# cheerlights.net
KiCad netlist of a schematic drawn in EAGLE
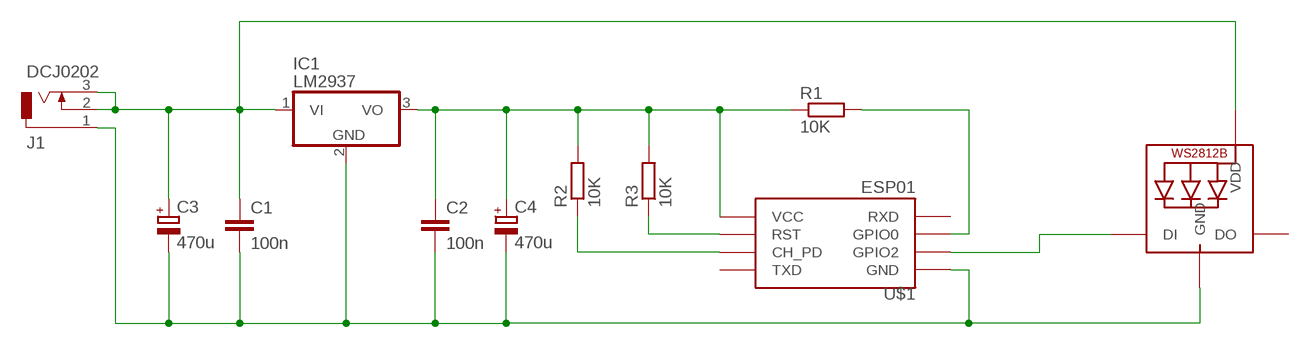
[diagram p0: schematic, sheet 1]

(export (version "E")
  (design (tool "Eeschema 10.0.6"))
  (components
    (comp (ref "C1")
      (value "100n")
      (footprint "eagle-import:C050-025X075")
      (libsource (lib "eagle-import") (part "C-EU050-025X075"))
    )
    (comp (ref "C2")
      (value "100n")
      (footprint "eagle-import:C050-025X075")
      (libsource (lib "eagle-import") (part "C-EU050-025X075"))
    )
    (comp (ref "C3")
      (value "470u")
      (footprint "eagle-import:E5-10,5")
      (libsource (lib "eagle-import") (part "CPOL-EUE5-10.5"))
    )
    (comp (ref "C4")
      (value "470u")
      (footprint "eagle-import:E5-10,5")
      (libsource (lib "eagle-import") (part "CPOL-EUE5-10.5"))
    )
    (comp (ref "IC1")
      (value "LM2937")
      (footprint "eagle-import:TO220H")
      (libsource (lib "eagle-import") (part "78T05"))
    )
    (comp (ref "J1")
      (value "DCJ0202")
      (footprint "eagle-import:DCJ0202")
      (libsource (lib "eagle-import") (part "DCJ0202"))
    )
    (comp (ref "LED1")
      (value "WS2812B_5050N")
      (footprint "eagle-import:WS2812B-NARROW")
      (libsource (lib "eagle-import") (part "WS2812B_5050N"))
    )
    (comp (ref "R1")
      (value "10K")
      (footprint "eagle-import:0207_10")
      (libsource (lib "eagle-import") (part "R-EU_0207/10"))
    )
    (comp (ref "R2")
      (value "10K")
      (footprint "eagle-import:0207_15")
      (libsource (lib "eagle-import") (part "R-EU_0207/15"))
    )
    (comp (ref "R3")
      (value "10K")
      (footprint "eagle-import:0207_15")
      (libsource (lib "eagle-import") (part "R-EU_0207/15"))
    )
    (comp (ref "U$1")
      (value "ESP01")
      (footprint "eagle-import:ESP01")
      (libsource (lib "eagle-import") (part "ESP01"))
    )
  )
  (nets
    (net (code "1") (name "Net-(IC1-GND)") (class "Default")
      (node (ref "C1") (pin "2") (pinfunction "2_2") (pintype "passive"))
      (node (ref "C2") (pin "2") (pinfunction "2_2") (pintype "passive"))
      (node (ref "C3") (pin "-") (pinfunction "-_-") (pintype "passive"))
      (node (ref "C4") (pin "-") (pinfunction "-_-") (pintype "passive"))
      (node (ref "IC1") (pin "2") (pinfunction "GND_2") (pintype "passive"))
      (node (ref "J1") (pin "1") (pinfunction "1_1") (pintype "passive"))
      (node (ref "LED1") (pin "3-GND") (pinfunction "GND_3-GND") (pintype "power_in"))
      (node (ref "U$1") (pin "GND") (pinfunction "GND_GND") (pintype "bidirectional"))
    )
    (net (code "2") (name "Net-(IC1-VI)") (class "Default")
      (node (ref "C1") (pin "1") (pinfunction "1_1") (pintype "passive"))
      (node (ref "C3") (pin "+") (pinfunction "+_+") (pintype "passive"))
      (node (ref "IC1") (pin "1") (pinfunction "VI_1") (pintype "input"))
      (node (ref "J1") (pin "2") (pinfunction "2_2") (pintype "passive"))
      (node (ref "J1") (pin "3") (pinfunction "3_3") (pintype "passive"))
      (node (ref "LED1") (pin "1-VDD") (pinfunction "VDD_1-VDD") (pintype "power_in"))
    )
    (net (code "3") (name "Net-(IC1-VO)") (class "Default")
      (node (ref "C2") (pin "1") (pinfunction "1_1") (pintype "passive"))
      (node (ref "C4") (pin "+") (pinfunction "+_+") (pintype "passive"))
      (node (ref "IC1") (pin "3") (pinfunction "VO_3") (pintype "passive"))
      (node (ref "R1") (pin "1") (pinfunction "1_1") (pintype "passive"))
      (node (ref "R2") (pin "2") (pinfunction "2_2") (pintype "passive"))
      (node (ref "R3") (pin "2") (pinfunction "2_2") (pintype "passive"))
      (node (ref "U$1") (pin "VCC") (pinfunction "VCC_VCC") (pintype "bidirectional"))
    )
    (net (code "4") (name "Net-(LED1-DI)") (class "Default")
      (node (ref "LED1") (pin "4-DIN") (pinfunction "DI_4-DIN") (pintype "input"))
      (node (ref "U$1") (pin "GPIO2") (pinfunction "GPIO2_GPIO2") (pintype "bidirectional"))
    )
    (net (code "5") (name "Net-(R1-Pad2)") (class "Default")
      (node (ref "R1") (pin "2") (pinfunction "2_2") (pintype "passive"))
      (node (ref "U$1") (pin "GPIO0") (pinfunction "GPIO0_GPIO0") (pintype "bidirectional"))
    )
    (net (code "6") (name "Net-(R2-Pad1)") (class "Default")
      (node (ref "R2") (pin "1") (pinfunction "1_1") (pintype "passive"))
      (node (ref "U$1") (pin "CH_PD") (pinfunction "CH_PD_CH_PD") (pintype "bidirectional"))
    )
    (net (code "7") (name "Net-(R3-Pad1)") (class "Default")
      (node (ref "R3") (pin "1") (pinfunction "1_1") (pintype "passive"))
      (node (ref "U$1") (pin "RST") (pinfunction "RST_RST") (pintype "bidirectional"))
    )
    (net (code "8") (name "unconnected-(LED1-DO-Pad2-DOUT)") (class "Default")
      (node (ref "LED1") (pin "2-DOUT") (pinfunction "DO_2-DOUT") (pintype "output"))
    )
    (net (code "9") (name "unconnected-(U$1-RXD-PadRX)") (class "Default")
      (node (ref "U$1") (pin "RX") (pinfunction "RXD_RX") (pintype "bidirectional"))
    )
    (net (code "10") (name "unconnected-(U$1-TXD-PadTX)") (class "Default")
      (node (ref "U$1") (pin "TX") (pinfunction "TXD_TX") (pintype "bidirectional"))
    )
  )
)
